# Arduino_Shield_V4_-_Small_-_7805_-_REG_-.net
KiCad netlist of a schematic drawn in EAGLE
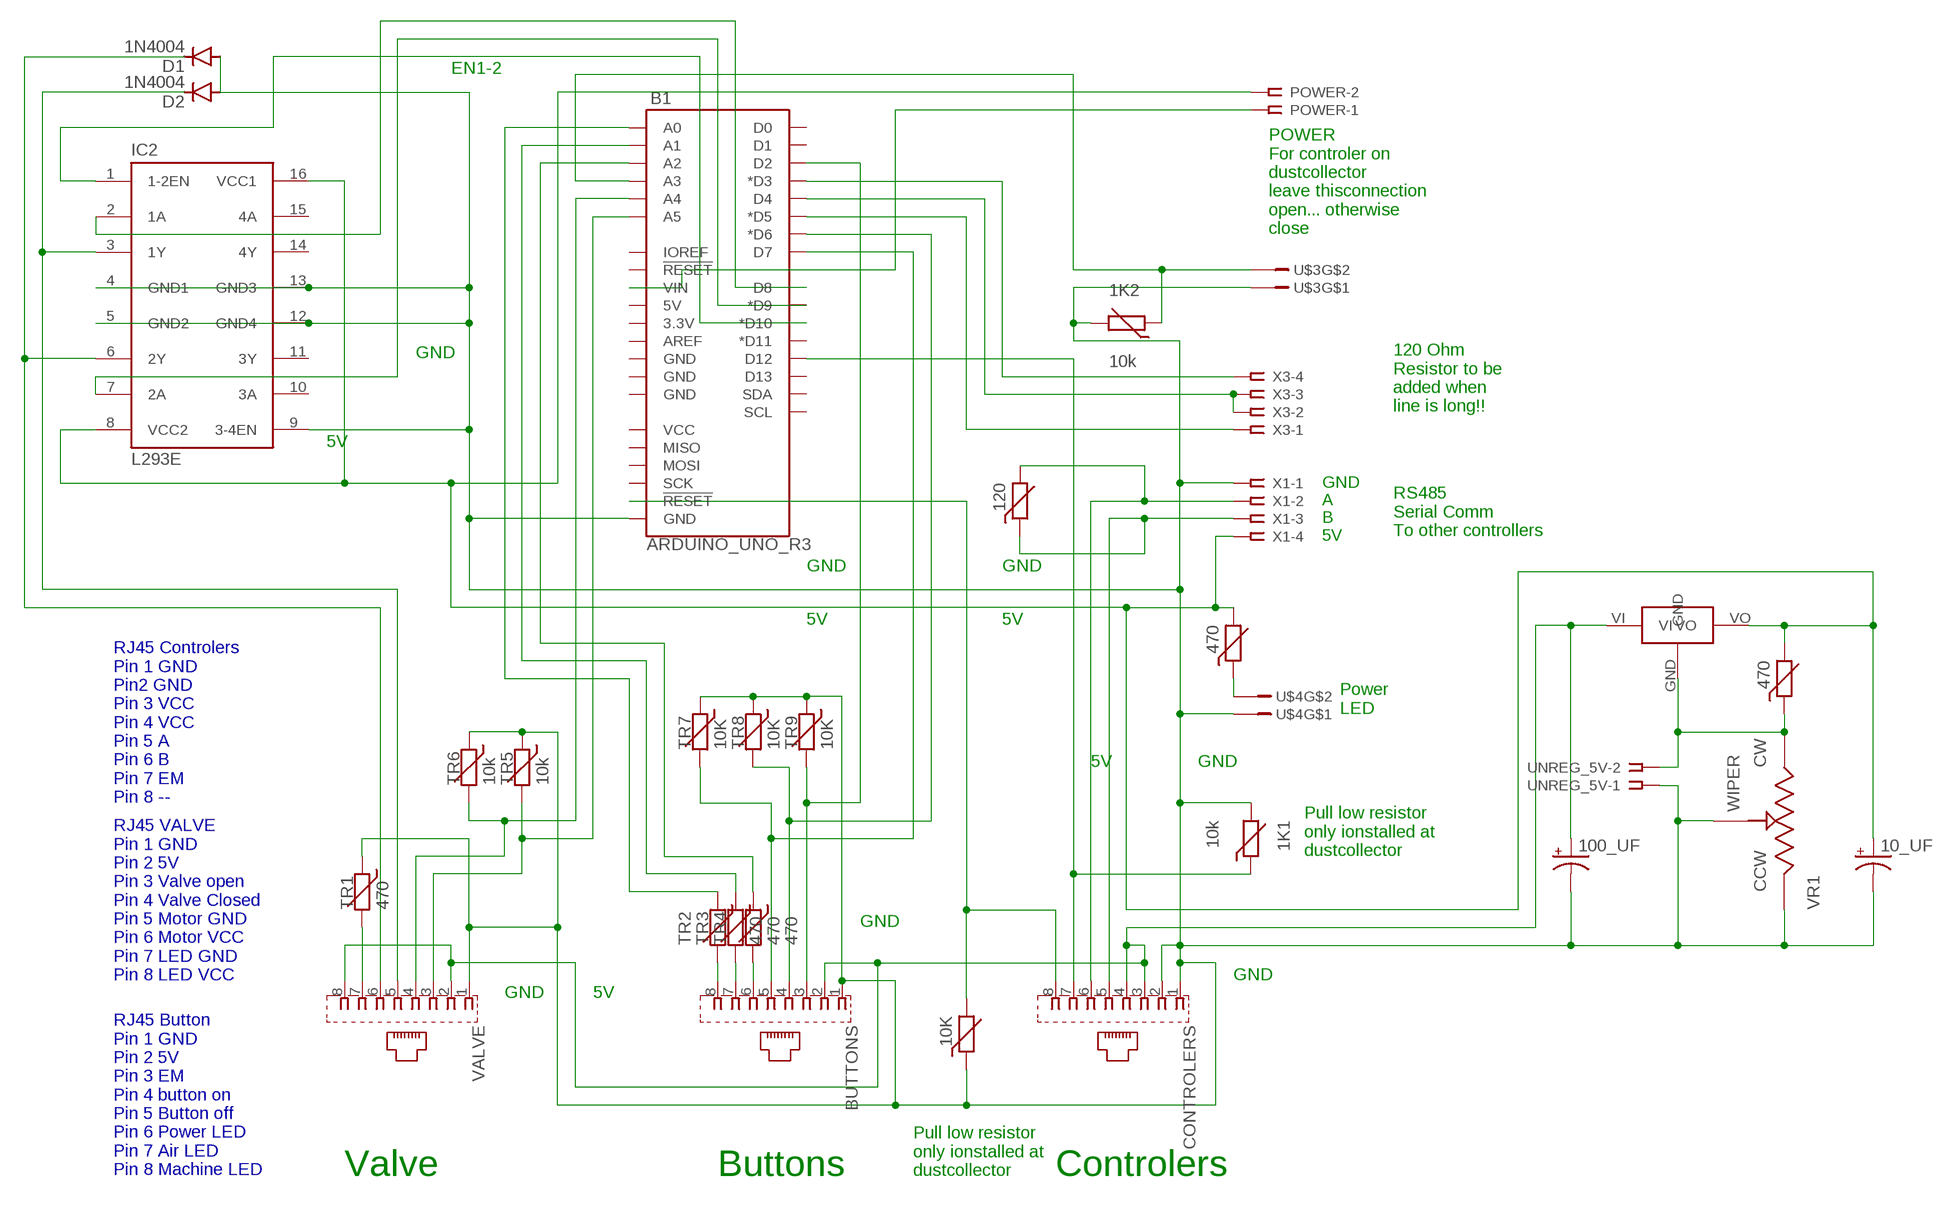
[diagram p0: schematic, sheet 1]

(export (version "E")
  (design (tool "Eeschema 10.0.6"))
  (components
    (comp (ref "1K")
      (value "470")
      (footprint "eagle-import:R-7,5")
      (libsource (lib "eagle-import") (part "THERMISTOR_R-7,5"))
    )
    (comp (ref "1K1")
      (value "10k")
      (footprint "eagle-import:R-7,5")
      (libsource (lib "eagle-import") (part "THERMISTOR_R-7,5"))
    )
    (comp (ref "1K2")
      (value "10k")
      (footprint "eagle-import:R-7,5")
      (libsource (lib "eagle-import") (part "THERMISTOR_R-7,5"))
    )
    (comp (ref "1K3")
      (value "120")
      (footprint "eagle-import:R-7,5")
      (libsource (lib "eagle-import") (part "THERMISTOR_R-7,5"))
    )
    (comp (ref "1K4")
      (value "470")
      (footprint "eagle-import:R-7,5")
      (libsource (lib "eagle-import") (part "THERMISTOR_R-7,5"))
    )
    (comp (ref "10K")
      (value "10K")
      (footprint "eagle-import:R-7,5")
      (libsource (lib "eagle-import") (part "THERMISTOR_R-7,5"))
    )
    (comp (ref "10_UF")
      (value "CPOL-USE2,5-6E")
      (footprint "eagle-import:E2,5-6E")
      (libsource (lib "eagle-import") (part "CPOL-USE2,5-6E"))
    )
    (comp (ref "100_UF")
      (value "CPOL-USE2,5-6E")
      (footprint "eagle-import:E2,5-6E")
      (libsource (lib "eagle-import") (part "CPOL-USE2,5-6E"))
    )
    (comp (ref "B1")
      (value "ARDUINO_UNO_R3")
      (footprint "eagle-import:ARDUINO_R3")
      (libsource (lib "eagle-import") (part "ARDUINO_UNO_R3"))
    )
    (comp (ref "BUTTONS")
      (value "GLX-S-88MRJ45")
      (footprint "eagle-import:GLX-S-88M")
      (libsource (lib "eagle-import") (part "GLX-S-88MRJ45"))
    )
    (comp (ref "CONTROLERS")
      (value "GLX-S-88MRJ45")
      (footprint "eagle-import:GLX-S-88M")
      (libsource (lib "eagle-import") (part "GLX-S-88MRJ45"))
    )
    (comp (ref "D1")
      (value "1N4004")
      (footprint "eagle-import:DO41-10")
      (libsource (lib "eagle-import") (part "1N4004"))
    )
    (comp (ref "D2")
      (value "1N4004")
      (footprint "eagle-import:DO41-10")
      (libsource (lib "eagle-import") (part "1N4004"))
    )
    (comp (ref "IC2")
      (value "L293E")
      (footprint "eagle-import:DIL16")
      (fields (field (name "MF") "Arrow Electronics"))
      (libsource (lib "eagle-import") (part "L293E"))
    )
    (comp (ref "POWER")
      (value "SSW-102-02-G-S")
      (footprint "eagle-import:SSW-102-02-G-S")
      (fields (field (name "MF") "Samtec Inc."))
      (libsource (lib "eagle-import") (part "SSW-102-02-G-S"))
    )
    (comp (ref "TR1")
      (value "470")
      (footprint "eagle-import:R-7,5")
      (libsource (lib "eagle-import") (part "THERMISTOR_R-7,5"))
    )
    (comp (ref "TR2")
      (value "470")
      (footprint "eagle-import:R-7,5")
      (libsource (lib "eagle-import") (part "THERMISTOR_R-7,5"))
    )
    (comp (ref "TR3")
      (value "470")
      (footprint "eagle-import:R-7,5")
      (libsource (lib "eagle-import") (part "THERMISTOR_R-7,5"))
    )
    (comp (ref "TR4")
      (value "470")
      (footprint "eagle-import:R-7,5")
      (libsource (lib "eagle-import") (part "THERMISTOR_R-7,5"))
    )
    (comp (ref "TR5")
      (value "10k")
      (footprint "eagle-import:R-7,5")
      (libsource (lib "eagle-import") (part "THERMISTOR_R-7,5"))
    )
    (comp (ref "TR6")
      (value "10k")
      (footprint "eagle-import:R-7,5")
      (libsource (lib "eagle-import") (part "THERMISTOR_R-7,5"))
    )
    (comp (ref "TR7")
      (value "10K")
      (footprint "eagle-import:R-7,5")
      (libsource (lib "eagle-import") (part "THERMISTOR_R-7,5"))
    )
    (comp (ref "TR8")
      (value "10K")
      (footprint "eagle-import:R-7,5")
      (libsource (lib "eagle-import") (part "THERMISTOR_R-7,5"))
    )
    (comp (ref "TR9")
      (value "10K")
      (footprint "eagle-import:R-7,5")
      (libsource (lib "eagle-import") (part "THERMISTOR_R-7,5"))
    )
    (comp (ref "U$1")
      (value "7805-TO220V")
      (footprint "eagle-import:TO220AV")
      (libsource (lib "eagle-import") (part "7805-TO220V"))
    )
    (comp (ref "U$3")
      (value "JST2")
      (footprint "eagle-import:HDRV2W64P254_1X2_712X508X838B")
      (libsource (lib "eagle-import") (part "JST2"))
    )
    (comp (ref "U$4")
      (value "JST2")
      (footprint "eagle-import:HDRV2W64P254_1X2_712X508X838B")
      (libsource (lib "eagle-import") (part "JST2"))
    )
    (comp (ref "UNREG_5V")
      (value "SSW-102-02-G-S")
      (footprint "eagle-import:SSW-102-02-G-S")
      (fields (field (name "MF") "Samtec Inc."))
      (libsource (lib "eagle-import") (part "SSW-102-02-G-S"))
    )
    (comp (ref "VALVE")
      (value "GLX-S-88MRJ45")
      (footprint "eagle-import:GLX-S-88M")
      (libsource (lib "eagle-import") (part "GLX-S-88MRJ45"))
    )
    (comp (ref "VR1")
      (value "3296W-1-103LF")
      (footprint "eagle-import:W")
      (fields
        (field (name "MANUFACTURER") "Bourns Inc")
        (field (name "POWER") "0.5W, 1/2W")
        (field (name "TOLERANCE") "10%")
      )
      (libsource (lib "eagle-import") (part "3296?-W1-103LF"))
    )
    (comp (ref "X1")
      (value "SSW-104-02-G-S")
      (footprint "eagle-import:SSW-104-02-G-S")
      (fields (field (name "MF") "Samtec Inc."))
      (libsource (lib "eagle-import") (part "SSW-104-02-G-S"))
    )
    (comp (ref "X3")
      (value "SSW-104-02-G-S")
      (footprint "eagle-import:SSW-104-02-G-S")
      (fields (field (name "MF") "Samtec Inc."))
      (libsource (lib "eagle-import") (part "SSW-104-02-G-S"))
    )
  )
  (nets
    (net (code "1") (name "Net-(1K1-Pad1)") (class "Default")
      (node (ref "1K1") (pin "1") (pinfunction "1_1") (pintype "passive"))
      (node (ref "B1") (pin "D12") (pinfunction "D12_D12") (pintype "bidirectional"))
      (node (ref "CONTROLERS") (pin "7") (pinfunction "7_7") (pintype "passive"))
    )
    (net (code "2") (name "Net-(10K-Pad2)") (class "Default")
      (node (ref "10K") (pin "2") (pinfunction "2_2") (pintype "passive"))
      (node (ref "B1") (pin "RESET@2") (pinfunction "~{RESET}_RESET@2") (pintype "bidirectional"))
      (node (ref "CONTROLERS") (pin "8") (pinfunction "8_8") (pintype "passive"))
    )
    (net (code "3") (name "Net-(100_UF-Pad+)") (class "Default")
      (node (ref "100_UF") (pin "+") (pinfunction "+_+") (pintype "passive"))
      (node (ref "BUTTONS") (pin "2") (pinfunction "2_2") (pintype "passive"))
      (node (ref "CONTROLERS") (pin "3") (pinfunction "3_3") (pintype "passive"))
      (node (ref "CONTROLERS") (pin "4") (pinfunction "4_4") (pintype "passive"))
      (node (ref "U$1") (pin "VI") (pinfunction "VI_VI") (pintype "input"))
      (node (ref "VALVE") (pin "2") (pinfunction "2_2") (pintype "passive"))
      (node (ref "VALVE") (pin "8") (pinfunction "8_8") (pintype "passive"))
    )
    (net (code "4") (name "Net-(B1-*D3)") (class "Default")
      (node (ref "B1") (pin "D3") (pinfunction "*D3_D3") (pintype "bidirectional"))
      (node (ref "X3") (pin "4") (pinfunction "1_4") (pintype "passive"))
    )
    (net (code "5") (name "Net-(B1-*D5)") (class "Default")
      (node (ref "B1") (pin "D5") (pinfunction "*D5_D5") (pintype "bidirectional"))
      (node (ref "X3") (pin "1") (pinfunction "1_1") (pintype "passive"))
    )
    (net (code "6") (name "Net-(B1-*D6)") (class "Default")
      (node (ref "B1") (pin "D6") (pinfunction "*D6_D6") (pintype "bidirectional"))
      (node (ref "BUTTONS") (pin "4") (pinfunction "4_4") (pintype "passive"))
      (node (ref "TR8") (pin "2") (pinfunction "2_2") (pintype "passive"))
    )
    (net (code "7") (name "Net-(B1-*D9)") (class "Default")
      (node (ref "B1") (pin "D9") (pinfunction "*D9_D9") (pintype "bidirectional"))
      (node (ref "IC2") (pin "7") (pinfunction "2A_7") (pintype "input"))
    )
    (net (code "8") (name "Net-(B1-*D10)") (class "Default")
      (node (ref "B1") (pin "D10") (pinfunction "*D10_D10") (pintype "bidirectional"))
      (node (ref "IC2") (pin "1") (pinfunction "1-2EN_1") (pintype "input"))
    )
    (net (code "9") (name "Net-(B1-PadA0)") (class "Default")
      (node (ref "B1") (pin "A0") (pinfunction "A0_A0") (pintype "bidirectional"))
      (node (ref "TR2") (pin "1") (pinfunction "1_1") (pintype "passive"))
    )
    (net (code "10") (name "Net-(B1-PadA1)") (class "Default")
      (node (ref "B1") (pin "A1") (pinfunction "A1_A1") (pintype "bidirectional"))
      (node (ref "TR3") (pin "1") (pinfunction "1_1") (pintype "passive"))
    )
    (net (code "11") (name "Net-(B1-PadA2)") (class "Default")
      (node (ref "B1") (pin "A2") (pinfunction "A2_A2") (pintype "bidirectional"))
      (node (ref "TR4") (pin "1") (pinfunction "1_1") (pintype "passive"))
    )
    (net (code "12") (name "Net-(B1-PadA4)") (class "Default")
      (node (ref "B1") (pin "A4") (pinfunction "A4_A4") (pintype "bidirectional"))
      (node (ref "TR6") (pin "2") (pinfunction "2_2") (pintype "passive"))
      (node (ref "VALVE") (pin "4") (pinfunction "4_4") (pintype "passive"))
    )
    (net (code "13") (name "Net-(B1-PadA5)") (class "Default")
      (node (ref "B1") (pin "A5") (pinfunction "A5_A5") (pintype "bidirectional"))
      (node (ref "TR5") (pin "2") (pinfunction "2_2") (pintype "passive"))
      (node (ref "VALVE") (pin "3") (pinfunction "3_3") (pintype "passive"))
    )
    (net (code "14") (name "Net-(B1-PadD2)") (class "Default")
      (node (ref "B1") (pin "D2") (pinfunction "D2_D2") (pintype "bidirectional"))
      (node (ref "BUTTONS") (pin "3") (pinfunction "3_3") (pintype "passive"))
      (node (ref "TR9") (pin "2") (pinfunction "2_2") (pintype "passive"))
    )
    (net (code "15") (name "Net-(B1-PadD7)") (class "Default")
      (node (ref "B1") (pin "D7") (pinfunction "D7_D7") (pintype "bidirectional"))
      (node (ref "BUTTONS") (pin "5") (pinfunction "5_5") (pintype "passive"))
      (node (ref "TR7") (pin "2") (pinfunction "2_2") (pintype "passive"))
    )
    (net (code "16") (name "Net-(B1-PadVIN)") (class "Default")
      (node (ref "B1") (pin "VIN") (pinfunction "VIN_VIN") (pintype "bidirectional"))
      (node (ref "POWER") (pin "1") (pinfunction "1_1") (pintype "passive"))
    )
    (net (code "17") (name "Net-(BUTTONS-Pad6)") (class "Default")
      (node (ref "BUTTONS") (pin "6") (pinfunction "6_6") (pintype "passive"))
      (node (ref "TR4") (pin "2") (pinfunction "2_2") (pintype "passive"))
    )
    (net (code "18") (name "Net-(BUTTONS-Pad7)") (class "Default")
      (node (ref "BUTTONS") (pin "7") (pinfunction "7_7") (pintype "passive"))
      (node (ref "TR3") (pin "2") (pinfunction "2_2") (pintype "passive"))
    )
    (net (code "19") (name "Net-(BUTTONS-Pad8)") (class "Default")
      (node (ref "BUTTONS") (pin "8") (pinfunction "8_8") (pintype "passive"))
      (node (ref "TR2") (pin "2") (pinfunction "2_2") (pintype "passive"))
    )
    (net (code "20") (name "Net-(IC2-1A)") (class "Default")
      (node (ref "B1") (pin "D8") (pinfunction "D8_D8") (pintype "bidirectional"))
      (node (ref "IC2") (pin "2") (pinfunction "1A_2") (pintype "input"))
    )
    (net (code "21") (name "Net-(IC2-1Y)") (class "Default")
      (node (ref "D2") (pin "C") (pinfunction "C_C") (pintype "passive"))
      (node (ref "IC2") (pin "3") (pinfunction "1Y_3") (pintype "output"))
      (node (ref "VALVE") (pin "5") (pinfunction "5_5") (pintype "passive"))
    )
    (net (code "22") (name "Net-(IC2-2Y)") (class "Default")
      (node (ref "D1") (pin "C") (pinfunction "C_C") (pintype "passive"))
      (node (ref "IC2") (pin "6") (pinfunction "2Y_6") (pintype "output"))
      (node (ref "VALVE") (pin "6") (pinfunction "6_6") (pintype "passive"))
    )
    (net (code "23") (name "Net-(IC2-3-4EN)") (class "Default")
      (node (ref "100_UF") (pin "-") (pinfunction "-_-") (pintype "passive"))
      (node (ref "10K") (pin "1") (pinfunction "1_1") (pintype "passive"))
      (node (ref "10_UF") (pin "-") (pinfunction "-_-") (pintype "passive"))
      (node (ref "1K1") (pin "2") (pinfunction "2_2") (pintype "passive"))
      (node (ref "1K2") (pin "2") (pinfunction "2_2") (pintype "passive"))
      (node (ref "B1") (pin "GND@1") (pinfunction "GND_GND@1") (pintype "bidirectional"))
      (node (ref "BUTTONS") (pin "1") (pinfunction "1_1") (pintype "passive"))
      (node (ref "CONTROLERS") (pin "1") (pinfunction "1_1") (pintype "passive"))
      (node (ref "CONTROLERS") (pin "2") (pinfunction "2_2") (pintype "passive"))
      (node (ref "D1") (pin "A") (pinfunction "A_A") (pintype "passive"))
      (node (ref "D2") (pin "A") (pinfunction "A_A") (pintype "passive"))
      (node (ref "IC2") (pin "12") (pinfunction "GND4_12") (pintype "power_in"))
      (node (ref "IC2") (pin "13") (pinfunction "GND3_13") (pintype "power_in"))
      (node (ref "IC2") (pin "4") (pinfunction "GND1_4") (pintype "power_in"))
      (node (ref "IC2") (pin "5") (pinfunction "GND2_5") (pintype "power_in"))
      (node (ref "IC2") (pin "9") (pinfunction "3-4EN_9") (pintype "input"))
      (node (ref "TR1") (pin "1") (pinfunction "1_1") (pintype "passive"))
      (node (ref "TR5") (pin "1") (pinfunction "1_1") (pintype "passive"))
      (node (ref "TR6") (pin "1") (pinfunction "1_1") (pintype "passive"))
      (node (ref "TR7") (pin "1") (pinfunction "1_1") (pintype "passive"))
      (node (ref "TR8") (pin "1") (pinfunction "1_1") (pintype "passive"))
      (node (ref "TR9") (pin "1") (pinfunction "1_1") (pintype "passive"))
      (node (ref "U$3") (pin "1") (pinfunction "1_1") (pintype "passive"))
      (node (ref "U$4") (pin "1") (pinfunction "1_1") (pintype "passive"))
      (node (ref "UNREG_5V") (pin "1") (pinfunction "1_1") (pintype "passive"))
      (node (ref "VALVE") (pin "1") (pinfunction "1_1") (pintype "passive"))
      (node (ref "VR1") (pin "1") (pinfunction "1_1") (pintype "passive"))
      (node (ref "VR1") (pin "2") (pinfunction "2_2") (pintype "passive"))
      (node (ref "X1") (pin "1") (pinfunction "1_1") (pintype "passive"))
    )
    (net (code "24") (name "Net-(IC2-VCC1)") (class "Default")
      (node (ref "10_UF") (pin "+") (pinfunction "+_+") (pintype "passive"))
      (node (ref "1K") (pin "2") (pinfunction "2_2") (pintype "passive"))
      (node (ref "1K4") (pin "2") (pinfunction "2_2") (pintype "passive"))
      (node (ref "IC2") (pin "16") (pinfunction "VCC1_16") (pintype "power_in"))
      (node (ref "IC2") (pin "8") (pinfunction "VCC2_8") (pintype "power_in"))
      (node (ref "POWER") (pin "2") (pinfunction "1_2") (pintype "passive"))
      (node (ref "U$1") (pin "VO") (pinfunction "VO_VO") (pintype "output"))
      (node (ref "X1") (pin "4") (pinfunction "1_4") (pintype "passive"))
    )
    (net (code "25") (name "Net-(TR1-Pad2)") (class "Default")
      (node (ref "TR1") (pin "2") (pinfunction "2_2") (pintype "passive"))
      (node (ref "VALVE") (pin "7") (pinfunction "7_7") (pintype "passive"))
    )
    (net (code "26") (name "Net-(U$3B-1)") (class "Default")
      (node (ref "1K2") (pin "1") (pinfunction "1_1") (pintype "passive"))
      (node (ref "B1") (pin "A3") (pinfunction "A3_A3") (pintype "bidirectional"))
      (node (ref "U$3") (pin "2") (pinfunction "1_2") (pintype "passive"))
    )
    (net (code "27") (name "Net-(U$4B-1)") (class "Default")
      (node (ref "1K") (pin "1") (pinfunction "1_1") (pintype "passive"))
      (node (ref "U$4") (pin "2") (pinfunction "1_2") (pintype "passive"))
    )
    (net (code "28") (name "Net-(UNREG_5VB-1)") (class "Default")
      (node (ref "1K4") (pin "1") (pinfunction "1_1") (pintype "passive"))
      (node (ref "U$1") (pin "GND") (pinfunction "GND_GND") (pintype "bidirectional"))
      (node (ref "UNREG_5V") (pin "2") (pinfunction "1_2") (pintype "passive"))
      (node (ref "VR1") (pin "3") (pinfunction "3_3") (pintype "passive"))
    )
    (net (code "29") (name "Net-(X1B-1)") (class "Default")
      (node (ref "1K3") (pin "2") (pinfunction "2_2") (pintype "passive"))
      (node (ref "CONTROLERS") (pin "6") (pinfunction "6_6") (pintype "passive"))
      (node (ref "X1") (pin "2") (pinfunction "1_2") (pintype "passive"))
    )
    (net (code "30") (name "Net-(X1C-1)") (class "Default")
      (node (ref "1K3") (pin "1") (pinfunction "1_1") (pintype "passive"))
      (node (ref "CONTROLERS") (pin "5") (pinfunction "5_5") (pintype "passive"))
      (node (ref "X1") (pin "3") (pinfunction "1_3") (pintype "passive"))
    )
    (net (code "31") (name "Net-(X3B-1)") (class "Default")
      (node (ref "B1") (pin "D4") (pinfunction "D4_D4") (pintype "bidirectional"))
      (node (ref "X3") (pin "2") (pinfunction "1_2") (pintype "passive"))
      (node (ref "X3") (pin "3") (pinfunction "1_3") (pintype "passive"))
    )
    (net (code "32") (name "unconnected-(B1-*D11-PadD11)") (class "Default")
      (node (ref "B1") (pin "D11") (pinfunction "*D11_D11") (pintype "bidirectional"))
    )
    (net (code "33") (name "unconnected-(B1-GND-PadGND@2)") (class "Default")
      (node (ref "B1") (pin "GND@2") (pinfunction "GND_GND@2") (pintype "bidirectional"))
    )
    (net (code "34") (name "unconnected-(B1-GND-PadGND@3)") (class "Default")
      (node (ref "B1") (pin "GND@3") (pinfunction "GND_GND@3") (pintype "bidirectional"))
    )
    (net (code "35") (name "unconnected-(B1-GND-PadGND@4)") (class "Default")
      (node (ref "B1") (pin "GND@4") (pinfunction "GND_GND@4") (pintype "bidirectional"))
    )
    (net (code "36") (name "unconnected-(B1-Pad3.3V)") (class "Default")
      (node (ref "B1") (pin "3.3V") (pinfunction "3.3V_3.3V") (pintype "bidirectional"))
    )
    (net (code "37") (name "unconnected-(B1-Pad5V)") (class "Default")
      (node (ref "B1") (pin "5V") (pinfunction "5V_5V") (pintype "bidirectional"))
    )
    (net (code "38") (name "unconnected-(B1-PadAREF)") (class "Default")
      (node (ref "B1") (pin "AREF") (pinfunction "AREF_AREF") (pintype "bidirectional"))
    )
    (net (code "39") (name "unconnected-(B1-PadD0)") (class "Default")
      (node (ref "B1") (pin "D0") (pinfunction "D0_D0") (pintype "bidirectional"))
    )
    (net (code "40") (name "unconnected-(B1-PadD1)") (class "Default")
      (node (ref "B1") (pin "D1") (pinfunction "D1_D1") (pintype "bidirectional"))
    )
    (net (code "41") (name "unconnected-(B1-PadD13)") (class "Default")
      (node (ref "B1") (pin "D13") (pinfunction "D13_D13") (pintype "bidirectional"))
    )
    (net (code "42") (name "unconnected-(B1-PadIOREF)") (class "Default")
      (node (ref "B1") (pin "IOREF") (pinfunction "IOREF_IOREF") (pintype "bidirectional"))
    )
    (net (code "43") (name "unconnected-(B1-PadMISO)") (class "Default")
      (node (ref "B1") (pin "MISO") (pinfunction "MISO_MISO") (pintype "bidirectional"))
    )
    (net (code "44") (name "unconnected-(B1-PadMOSI)") (class "Default")
      (node (ref "B1") (pin "MOSI") (pinfunction "MOSI_MOSI") (pintype "bidirectional"))
    )
    (net (code "45") (name "unconnected-(B1-PadSCK)") (class "Default")
      (node (ref "B1") (pin "SCK") (pinfunction "SCK_SCK") (pintype "bidirectional"))
    )
    (net (code "46") (name "unconnected-(B1-PadSCL)") (class "Default")
      (node (ref "B1") (pin "SCL") (pinfunction "SCL_SCL") (pintype "bidirectional"))
    )
    (net (code "47") (name "unconnected-(B1-PadSDA)") (class "Default")
      (node (ref "B1") (pin "SDA") (pinfunction "SDA_SDA") (pintype "bidirectional"))
    )
    (net (code "48") (name "unconnected-(B1-PadVCC)") (class "Default")
      (node (ref "B1") (pin "VCC") (pinfunction "VCC_VCC") (pintype "bidirectional"))
    )
    (net (code "49") (name "unconnected-(B1-~{RESET}-PadRESET@1)") (class "Default")
      (node (ref "B1") (pin "RESET@1") (pinfunction "~{RESET}_RESET@1") (pintype "bidirectional"))
    )
    (net (code "50") (name "unconnected-(IC2-3A-Pad10)") (class "Default")
      (node (ref "IC2") (pin "10") (pinfunction "3A_10") (pintype "input"))
    )
    (net (code "51") (name "unconnected-(IC2-3Y-Pad11)") (class "Default")
      (node (ref "IC2") (pin "11") (pinfunction "3Y_11") (pintype "output"))
    )
    (net (code "52") (name "unconnected-(IC2-4A-Pad15)") (class "Default")
      (node (ref "IC2") (pin "15") (pinfunction "4A_15") (pintype "input"))
    )
    (net (code "53") (name "unconnected-(IC2-4Y-Pad14)") (class "Default")
      (node (ref "IC2") (pin "14") (pinfunction "4Y_14") (pintype "output"))
    )
  )
)
